# Hambmark_PCB-practice-STM32-two-wheel-ba.net
KiCad netlist of a schematic drawn in Altium Designer
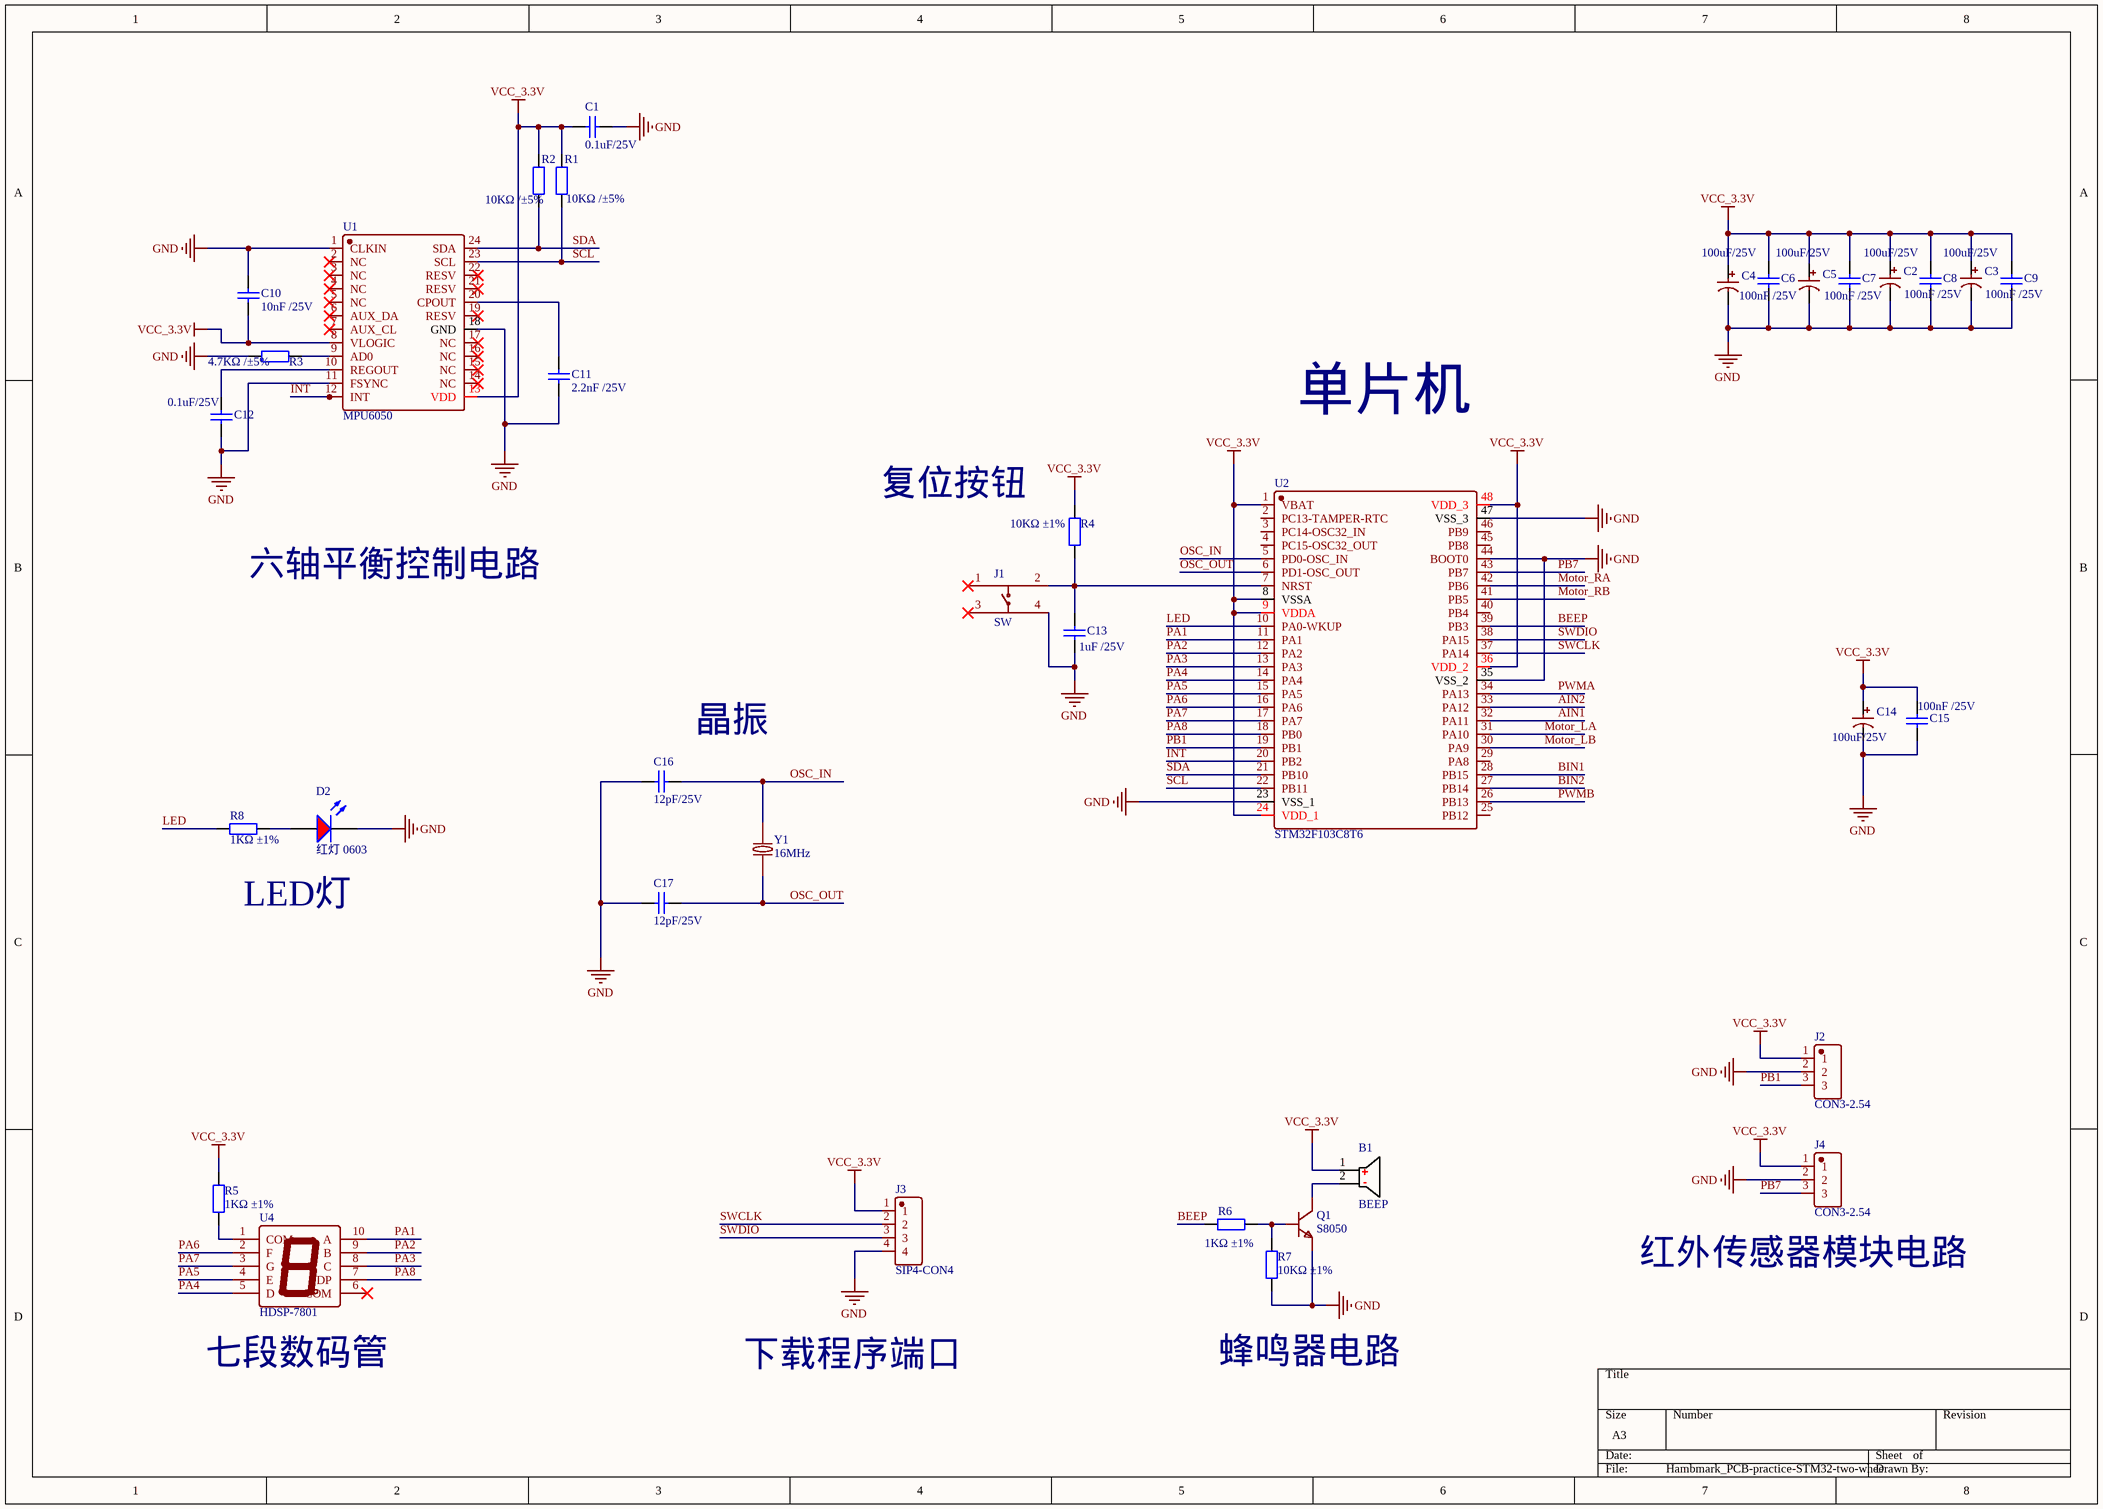
[diagram p0: Hambmark_PCB-practice-STM32-two-wheel-balancing-car__PRJ__2_BalanceControl.SchDoc]

(export (version "E")
  (design (tool "Eeschema 10.0.6"))
  (components
    (comp (ref "B1") (value "BEEP") (footprint "BEEP-9MM") (libsource (lib "Other") (part "BEEP")))
    (comp (ref "C1")
      (value "0.1uF/25V")
      (footprint "C0603")
      (description "贴片电容")
      (libsource (lib "Cap") (part "1206 100nF (104) 10% 50V"))
    )
    (comp (ref "C2") (value "100uF/25V") (footprint "C0603") (libsource (lib "Other") (part "100uF/25V")))
    (comp (ref "C3") (value "100uF/25V") (footprint "C0603") (libsource (lib "Other") (part "100uF/25V")))
    (comp (ref "C4") (value "100uF/25V") (footprint "C0603") (libsource (lib "Other") (part "100uF/25V")))
    (comp (ref "C5") (value "100uF/25V") (footprint "C0603") (libsource (lib "Other") (part "100uF/25V")))
    (comp (ref "C6")
      (value "100nF /25V")
      (footprint "C0603")
      (description "贴片电容")
      (libsource (lib "Cap") (part "0402 20pF (200) 5% 50V"))
    )
    (comp (ref "C7")
      (value "100nF /25V")
      (footprint "C0603")
      (description "贴片电容")
      (libsource (lib "Cap") (part "0402 20pF (200) 5% 50V"))
    )
    (comp (ref "C8")
      (value "100nF /25V")
      (footprint "C0603")
      (description "贴片电容")
      (libsource (lib "Cap") (part "0402 20pF (200) 5% 50V"))
    )
    (comp (ref "C9")
      (value "100nF /25V")
      (footprint "C0603")
      (description "贴片电容")
      (libsource (lib "Cap") (part "0402 20pF (200) 5% 50V"))
    )
    (comp (ref "C10")
      (value "10nF /25V")
      (footprint "C0603")
      (description "贴片电容")
      (libsource (lib "Cap") (part "1206 100nF (104) 10% 50V"))
    )
    (comp (ref "C11")
      (value "2.2nF /25V")
      (footprint "C0603")
      (description "贴片电容")
      (libsource (lib "Cap") (part "1206 100nF (104) 10% 50V"))
    )
    (comp (ref "C12")
      (value "0.1uF/25V")
      (footprint "C0603")
      (description "贴片电容")
      (libsource (lib "Cap") (part "1206 100nF (104) 10% 50V"))
    )
    (comp (ref "C13")
      (value "1uF /25V")
      (footprint "C0603")
      (description "贴片电容")
      (libsource (lib "Cap") (part "0402 20pF (200) 5% 50V"))
    )
    (comp (ref "C14") (value "100uF/25V") (footprint "C0603") (libsource (lib "Other") (part "100uF/25V")))
    (comp (ref "C15")
      (value "100nF /25V")
      (footprint "C0603")
      (description "贴片电容")
      (libsource (lib "Cap") (part "1206 100nF (104) 10% 50V"))
    )
    (comp (ref "C16")
      (value "12pF/25V")
      (footprint "C0603")
      (description "贴片电容")
      (libsource (lib "Cap") (part "0805 100nF(104) 10% 50V"))
    )
    (comp (ref "C17")
      (value "12pF/25V")
      (footprint "C0603")
      (description "贴片电容")
      (libsource (lib "Cap") (part "0805 100nF(104) 10% 50V"))
    )
    (comp (ref "D2")
      (value "红灯 0603")
      (footprint "LED-0603_S1")
      (description "发光二极管")
      (libsource (lib "LED") (part "0603 红灯"))
    )
    (comp (ref "J1") (value "SW") (footprint "SW-SMD_4P-L6.0-W6.0") (libsource (lib "Other") (part "SW")))
    (comp (ref "J2")
      (value "CON3-2.54")
      (footprint "DIP-3P-2.54-W")
      (libsource (lib "Other") (part "CON3-2.54"))
    )
    (comp (ref "J3")
      (value "SIP4-CON4")
      (footprint "DIP-4P-2.54-N")
      (libsource (lib "Other") (part "SIP4-CON4"))
    )
    (comp (ref "J4")
      (value "CON3-2.54")
      (footprint "DIP-3P-2.54-W")
      (libsource (lib "Other") (part "CON3-2.54"))
    )
    (comp (ref "Q1") (value "S8050") (footprint "SOT-23-3") (libsource (lib "Other") (part "S8050")))
    (comp (ref "R1")
      (value "10KΩ /±5%")
      (footprint "R0603")
      (description "贴片电阻")
      (libsource (lib "") (part "0402 0Ω (0R0) 1%_1"))
    )
    (comp (ref "R2")
      (value "10KΩ /±5%")
      (footprint "R0603")
      (description "贴片电阻")
      (libsource (lib "") (part "0402 0Ω (0R0) 1%_1"))
    )
    (comp (ref "R3")
      (value "4.7KΩ /±5%")
      (footprint "R0603")
      (description "贴片电阻")
      (libsource (lib "RES") (part "0402 0Ω (0R0) 1%"))
    )
    (comp (ref "R4")
      (value "10KΩ ±1%")
      (footprint "R0603")
      (description "贴片电阻")
      (libsource (lib "") (part "0402 0Ω (0R0) 1%_1"))
    )
    (comp (ref "R5")
      (value "1KΩ ±1%")
      (footprint "R0603")
      (description "贴片电阻")
      (libsource (lib "RES") (part "0603 1KΩ (1001) 1%"))
    )
    (comp (ref "R6")
      (value "1KΩ ±1%")
      (footprint "R0603")
      (description "贴片电阻")
      (libsource (lib "") (part "0603 1KΩ (1001) 1%_1"))
    )
    (comp (ref "R7")
      (value "10KΩ ±1%")
      (footprint "R0603")
      (description "贴片电阻")
      (libsource (lib "") (part "0603 1KΩ (1001) 1%_3"))
    )
    (comp (ref "R8")
      (value "1KΩ ±1%")
      (footprint "R0603")
      (description "贴片电阻")
      (libsource (lib "") (part "0603 1KΩ (1001) 1%_2"))
    )
    (comp (ref "U1")
      (value "MPU6050")
      (footprint "QFN-24_L4.0-W4.0-P0.50-BL")
      (libsource (lib "Other") (part "MPU6050"))
    )
    (comp (ref "U2")
      (value "STM32F103C8T6")
      (footprint "LQFP-48_L7.0-W7.0")
      (libsource (lib "Other") (part "STM32F103C8T6"))
    )
    (comp (ref "U4")
      (value "HDSP-7801")
      (footprint "LED-SEG-SMD_HDSP-7801")
      (libsource (lib "Other") (part "HDSP-7801"))
    )
    (comp (ref "Y1")
      (value "16MHz")
      (footprint "CRYSTAL-SMD_L3.2-W1.5")
      (libsource (lib "Other") (part "FC-135R 32.7680KF"))
    )
  )
  (nets
    (net (code "1") (name "/AIN1") (class "Default")
      (node (ref "U2") (pin "32") (pinfunction "PA11_32") (pintype "passive"))
    )
    (net (code "2") (name "/AIN2") (class "Default")
      (node (ref "U2") (pin "33") (pinfunction "PA12_33") (pintype "passive"))
    )
    (net (code "3") (name "/BEEP") (class "Default")
      (node (ref "R6") (pin "1") (pinfunction "1_1") (pintype "passive"))
      (node (ref "U2") (pin "39") (pinfunction "PB3_39") (pintype "passive"))
    )
    (net (code "4") (name "/BIN1") (class "Default")
      (node (ref "U2") (pin "28") (pinfunction "PB15_28") (pintype "passive"))
    )
    (net (code "5") (name "/BIN2") (class "Default")
      (node (ref "U2") (pin "27") (pinfunction "PB14_27") (pintype "passive"))
    )
    (net (code "6") (name "/INT") (class "Default")
      (node (ref "U1") (pin "12") (pinfunction "INT_12") (pintype "passive"))
      (node (ref "U2") (pin "20") (pinfunction "PB2_20") (pintype "passive"))
    )
    (net (code "7") (name "/LED") (class "Default")
      (node (ref "R8") (pin "2") (pinfunction "2_2") (pintype "passive"))
      (node (ref "U2") (pin "10") (pinfunction "PA0-WKUP_10") (pintype "passive"))
    )
    (net (code "8") (name "/Motor_LA") (class "Default")
      (node (ref "U2") (pin "31") (pinfunction "PA10_31") (pintype "passive"))
    )
    (net (code "9") (name "/Motor_LB") (class "Default")
      (node (ref "U2") (pin "30") (pinfunction "PA9_30") (pintype "passive"))
    )
    (net (code "10") (name "/Motor_RA") (class "Default")
      (node (ref "U2") (pin "42") (pinfunction "PB6_42") (pintype "passive"))
    )
    (net (code "11") (name "/Motor_RB") (class "Default")
      (node (ref "U2") (pin "41") (pinfunction "PB5_41") (pintype "passive"))
    )
    (net (code "12") (name "/OSC_IN") (class "Default")
      (node (ref "C16") (pin "1") (pinfunction "1_1") (pintype "passive"))
      (node (ref "U2") (pin "5") (pinfunction "PD0-OSC_IN_5") (pintype "passive"))
      (node (ref "Y1") (pin "2") (pinfunction "2_2") (pintype "passive"))
    )
    (net (code "13") (name "/OSC_OUT") (class "Default")
      (node (ref "C17") (pin "1") (pinfunction "1_1") (pintype "passive"))
      (node (ref "U2") (pin "6") (pinfunction "PD1-OSC_OUT_6") (pintype "passive"))
      (node (ref "Y1") (pin "1") (pinfunction "1_1") (pintype "passive"))
    )
    (net (code "14") (name "/PA1") (class "Default")
      (node (ref "U2") (pin "11") (pinfunction "PA1_11") (pintype "passive"))
      (node (ref "U4") (pin "10") (pinfunction "A_10") (pintype "passive"))
    )
    (net (code "15") (name "/PA2") (class "Default")
      (node (ref "U2") (pin "12") (pinfunction "PA2_12") (pintype "passive"))
      (node (ref "U4") (pin "9") (pinfunction "B_9") (pintype "passive"))
    )
    (net (code "16") (name "/PA3") (class "Default")
      (node (ref "U2") (pin "13") (pinfunction "PA3_13") (pintype "passive"))
      (node (ref "U4") (pin "8") (pinfunction "C_8") (pintype "passive"))
    )
    (net (code "17") (name "/PA4") (class "Default")
      (node (ref "U2") (pin "14") (pinfunction "PA4_14") (pintype "passive"))
      (node (ref "U4") (pin "5") (pinfunction "D_5") (pintype "passive"))
    )
    (net (code "18") (name "/PA5") (class "Default")
      (node (ref "U2") (pin "15") (pinfunction "PA5_15") (pintype "passive"))
      (node (ref "U4") (pin "4") (pinfunction "E_4") (pintype "passive"))
    )
    (net (code "19") (name "/PA6") (class "Default")
      (node (ref "U2") (pin "16") (pinfunction "PA6_16") (pintype "passive"))
      (node (ref "U4") (pin "2") (pinfunction "F_2") (pintype "passive"))
    )
    (net (code "20") (name "/PA7") (class "Default")
      (node (ref "U2") (pin "17") (pinfunction "PA7_17") (pintype "passive"))
      (node (ref "U4") (pin "3") (pinfunction "G_3") (pintype "passive"))
    )
    (net (code "21") (name "/PA8") (class "Default")
      (node (ref "U2") (pin "18") (pinfunction "PB0_18") (pintype "passive"))
      (node (ref "U4") (pin "7") (pinfunction "DP_7") (pintype "passive"))
    )
    (net (code "22") (name "/PB1") (class "Default")
      (node (ref "J2") (pin "3") (pinfunction "3_3") (pintype "passive"))
      (node (ref "U2") (pin "19") (pinfunction "PB1_19") (pintype "passive"))
    )
    (net (code "23") (name "/PB7") (class "Default")
      (node (ref "J4") (pin "3") (pinfunction "3_3") (pintype "passive"))
      (node (ref "U2") (pin "43") (pinfunction "PB7_43") (pintype "passive"))
    )
    (net (code "24") (name "/PWMA") (class "Default")
      (node (ref "U2") (pin "34") (pinfunction "PA13_34") (pintype "passive"))
    )
    (net (code "25") (name "/PWMB") (class "Default")
      (node (ref "U2") (pin "26") (pinfunction "PB13_26") (pintype "passive"))
    )
    (net (code "26") (name "/SCL") (class "Default")
      (node (ref "R1") (pin "1") (pinfunction "1_1") (pintype "passive"))
      (node (ref "U1") (pin "23") (pinfunction "SCL_23") (pintype "passive"))
      (node (ref "U2") (pin "22") (pinfunction "PB11_22") (pintype "passive"))
    )
    (net (code "27") (name "/SDA") (class "Default")
      (node (ref "R2") (pin "1") (pinfunction "1_1") (pintype "passive"))
      (node (ref "U1") (pin "24") (pinfunction "SDA_24") (pintype "passive"))
      (node (ref "U2") (pin "21") (pinfunction "PB10_21") (pintype "passive"))
    )
    (net (code "28") (name "/SWCLK") (class "Default")
      (node (ref "J3") (pin "2") (pinfunction "2_2") (pintype "passive"))
      (node (ref "U2") (pin "37") (pinfunction "PA14_37") (pintype "passive"))
    )
    (net (code "29") (name "/SWDIO") (class "Default")
      (node (ref "J3") (pin "3") (pinfunction "3_3") (pintype "passive"))
      (node (ref "U2") (pin "38") (pinfunction "PA15_38") (pintype "passive"))
    )
    (net (code "30") (name "GND") (class "Default")
      (node (ref "C1") (pin "2") (pinfunction "2_2") (pintype "passive"))
      (node (ref "C10") (pin "2") (pinfunction "2_2") (pintype "passive"))
      (node (ref "C11") (pin "1") (pinfunction "1_1") (pintype "passive"))
      (node (ref "C12") (pin "1") (pinfunction "1_1") (pintype "passive"))
      (node (ref "C13") (pin "2") (pinfunction "2_2") (pintype "passive"))
      (node (ref "C14") (pin "2") (pinfunction "2_2") (pintype "passive"))
      (node (ref "C15") (pin "1") (pinfunction "1_1") (pintype "passive"))
      (node (ref "C16") (pin "2") (pinfunction "2_2") (pintype "passive"))
      (node (ref "C17") (pin "2") (pinfunction "2_2") (pintype "passive"))
      (node (ref "C2") (pin "2") (pinfunction "2_2") (pintype "passive"))
      (node (ref "C3") (pin "2") (pinfunction "2_2") (pintype "passive"))
      (node (ref "C4") (pin "2") (pinfunction "2_2") (pintype "passive"))
      (node (ref "C5") (pin "2") (pinfunction "2_2") (pintype "passive"))
      (node (ref "C6") (pin "1") (pinfunction "1_1") (pintype "passive"))
      (node (ref "C7") (pin "1") (pinfunction "1_1") (pintype "passive"))
      (node (ref "C8") (pin "1") (pinfunction "1_1") (pintype "passive"))
      (node (ref "C9") (pin "1") (pinfunction "1_1") (pintype "passive"))
      (node (ref "D2") (pin "K") (pinfunction "K_K") (pintype "passive"))
      (node (ref "J1") (pin "4") (pinfunction "4_4") (pintype "passive"))
      (node (ref "J2") (pin "2") (pinfunction "2_2") (pintype "passive"))
      (node (ref "J3") (pin "4") (pinfunction "4_4") (pintype "passive"))
      (node (ref "J4") (pin "2") (pinfunction "2_2") (pintype "passive"))
      (node (ref "Q1") (pin "2") (pinfunction "E_2") (pintype "passive"))
      (node (ref "R3") (pin "2") (pinfunction "2_2") (pintype "passive"))
      (node (ref "R7") (pin "1") (pinfunction "1_1") (pintype "passive"))
      (node (ref "U1") (pin "1") (pinfunction "CLKIN_1") (pintype "passive"))
      (node (ref "U1") (pin "11") (pinfunction "FSYNC_11") (pintype "passive"))
      (node (ref "U1") (pin "18") (pinfunction "GND_18") (pintype "passive"))
      (node (ref "U2") (pin "23") (pinfunction "VSS_1_23") (pintype "passive"))
      (node (ref "U2") (pin "35") (pinfunction "VSS_2_35") (pintype "passive"))
      (node (ref "U2") (pin "44") (pinfunction "BOOT0_44") (pintype "passive"))
      (node (ref "U2") (pin "47") (pinfunction "VSS_3_47") (pintype "passive"))
    )
    (net (code "31") (name "Net-(D2-PadA)") (class "Default")
      (node (ref "D2") (pin "A") (pinfunction "A_A") (pintype "passive"))
      (node (ref "R8") (pin "1") (pinfunction "1_1") (pintype "passive"))
    )
    (net (code "32") (name "Net-(Q1-B)") (class "Default")
      (node (ref "Q1") (pin "1") (pinfunction "B_1") (pintype "passive"))
      (node (ref "R6") (pin "2") (pinfunction "2_2") (pintype "passive"))
      (node (ref "R7") (pin "2") (pinfunction "2_2") (pintype "passive"))
    )
    (net (code "33") (name "Net-(Q1-C)") (class "Default")
      (node (ref "B1") (pin "2") (pinfunction "2_2") (pintype "passive"))
      (node (ref "Q1") (pin "3") (pinfunction "C_3") (pintype "passive"))
    )
    (net (code "34") (name "Net-(R5-Pad2)") (class "Default")
      (node (ref "R5") (pin "2") (pinfunction "2_2") (pintype "passive"))
      (node (ref "U4") (pin "1") (pinfunction "COM_1") (pintype "passive"))
    )
    (net (code "35") (name "Net-(U1-AD0)") (class "Default")
      (node (ref "R3") (pin "1") (pinfunction "1_1") (pintype "passive"))
      (node (ref "U1") (pin "9") (pinfunction "AD0_9") (pintype "passive"))
    )
    (net (code "36") (name "Net-(U1-CPOUT)") (class "Default")
      (node (ref "C11") (pin "2") (pinfunction "2_2") (pintype "passive"))
      (node (ref "U1") (pin "20") (pinfunction "CPOUT_20") (pintype "passive"))
    )
    (net (code "37") (name "Net-(U1-REGOUT)") (class "Default")
      (node (ref "C12") (pin "2") (pinfunction "2_2") (pintype "passive"))
      (node (ref "U1") (pin "10") (pinfunction "REGOUT_10") (pintype "passive"))
    )
    (net (code "38") (name "Net-(U2-NRST)") (class "Default")
      (node (ref "C13") (pin "1") (pinfunction "1_1") (pintype "passive"))
      (node (ref "J1") (pin "2") (pinfunction "2_2") (pintype "passive"))
      (node (ref "R4") (pin "1") (pinfunction "1_1") (pintype "passive"))
      (node (ref "U2") (pin "7") (pinfunction "NRST_7") (pintype "passive"))
    )
    (net (code "39") (name "VCC_3.3V") (class "Default")
      (node (ref "B1") (pin "1") (pinfunction "1_1") (pintype "passive"))
      (node (ref "C1") (pin "1") (pinfunction "1_1") (pintype "passive"))
      (node (ref "C10") (pin "1") (pinfunction "1_1") (pintype "passive"))
      (node (ref "C14") (pin "1") (pinfunction "1_1") (pintype "passive"))
      (node (ref "C15") (pin "2") (pinfunction "2_2") (pintype "passive"))
      (node (ref "C2") (pin "1") (pinfunction "1_1") (pintype "passive"))
      (node (ref "C3") (pin "1") (pinfunction "1_1") (pintype "passive"))
      (node (ref "C4") (pin "1") (pinfunction "1_1") (pintype "passive"))
      (node (ref "C5") (pin "1") (pinfunction "1_1") (pintype "passive"))
      (node (ref "C6") (pin "2") (pinfunction "2_2") (pintype "passive"))
      (node (ref "C7") (pin "2") (pinfunction "2_2") (pintype "passive"))
      (node (ref "C8") (pin "2") (pinfunction "2_2") (pintype "passive"))
      (node (ref "C9") (pin "2") (pinfunction "2_2") (pintype "passive"))
      (node (ref "J2") (pin "1") (pinfunction "1_1") (pintype "passive"))
      (node (ref "J3") (pin "1") (pinfunction "1_1") (pintype "passive"))
      (node (ref "J4") (pin "1") (pinfunction "1_1") (pintype "passive"))
      (node (ref "R1") (pin "2") (pinfunction "2_2") (pintype "passive"))
      (node (ref "R2") (pin "2") (pinfunction "2_2") (pintype "passive"))
      (node (ref "R4") (pin "2") (pinfunction "2_2") (pintype "passive"))
      (node (ref "R5") (pin "1") (pinfunction "1_1") (pintype "passive"))
      (node (ref "U1") (pin "13") (pinfunction "VDD_13") (pintype "passive"))
      (node (ref "U1") (pin "8") (pinfunction "VLOGIC_8") (pintype "passive"))
      (node (ref "U2") (pin "1") (pinfunction "VBAT_1") (pintype "passive"))
      (node (ref "U2") (pin "24") (pinfunction "VDD_1_24") (pintype "passive"))
      (node (ref "U2") (pin "36") (pinfunction "VDD_2_36") (pintype "passive"))
      (node (ref "U2") (pin "48") (pinfunction "VDD_3_48") (pintype "passive"))
      (node (ref "U2") (pin "8") (pinfunction "VSSA_8") (pintype "passive"))
      (node (ref "U2") (pin "9") (pinfunction "VDDA_9") (pintype "passive"))
    )
    (net (code "40") (name "unconnected-(J1-Pad1)") (class "Default")
      (node (ref "J1") (pin "1") (pinfunction "1_1") (pintype "passive+no_connect"))
    )
    (net (code "41") (name "unconnected-(J1-Pad3)") (class "Default")
      (node (ref "J1") (pin "3") (pinfunction "3_3") (pintype "passive+no_connect"))
    )
    (net (code "42") (name "unconnected-(U1-AUX_CL-Pad7)") (class "Default")
      (node (ref "U1") (pin "7") (pinfunction "AUX_CL_7") (pintype "passive+no_connect"))
    )
    (net (code "43") (name "unconnected-(U1-AUX_DA-Pad6)") (class "Default")
      (node (ref "U1") (pin "6") (pinfunction "AUX_DA_6") (pintype "passive+no_connect"))
    )
    (net (code "44") (name "unconnected-(U1-NC-Pad2)") (class "Default")
      (node (ref "U1") (pin "2") (pinfunction "NC_2") (pintype "passive+no_connect"))
    )
    (net (code "45") (name "unconnected-(U1-NC-Pad3)") (class "Default")
      (node (ref "U1") (pin "3") (pinfunction "NC_3") (pintype "passive+no_connect"))
    )
    (net (code "46") (name "unconnected-(U1-NC-Pad4)") (class "Default")
      (node (ref "U1") (pin "4") (pinfunction "NC_4") (pintype "passive+no_connect"))
    )
    (net (code "47") (name "unconnected-(U1-NC-Pad5)") (class "Default")
      (node (ref "U1") (pin "5") (pinfunction "NC_5") (pintype "passive+no_connect"))
    )
    (net (code "48") (name "unconnected-(U1-NC-Pad14)") (class "Default")
      (node (ref "U1") (pin "14") (pinfunction "NC_14") (pintype "passive+no_connect"))
    )
    (net (code "49") (name "unconnected-(U1-NC-Pad15)") (class "Default")
      (node (ref "U1") (pin "15") (pinfunction "NC_15") (pintype "passive+no_connect"))
    )
    (net (code "50") (name "unconnected-(U1-NC-Pad16)") (class "Default")
      (node (ref "U1") (pin "16") (pinfunction "NC_16") (pintype "passive+no_connect"))
    )
    (net (code "51") (name "unconnected-(U1-NC-Pad17)") (class "Default")
      (node (ref "U1") (pin "17") (pinfunction "NC_17") (pintype "passive+no_connect"))
    )
    (net (code "52") (name "unconnected-(U1-RESV-Pad19)") (class "Default")
      (node (ref "U1") (pin "19") (pinfunction "RESV_19") (pintype "passive+no_connect"))
    )
    (net (code "53") (name "unconnected-(U1-RESV-Pad21)") (class "Default")
      (node (ref "U1") (pin "21") (pinfunction "RESV_21") (pintype "passive+no_connect"))
    )
    (net (code "54") (name "unconnected-(U1-RESV-Pad22)") (class "Default")
      (node (ref "U1") (pin "22") (pinfunction "RESV_22") (pintype "passive+no_connect"))
    )
    (net (code "55") (name "unconnected-(U2-PA8-Pad29)") (class "Default")
      (node (ref "U2") (pin "29") (pinfunction "PA8_29") (pintype "passive"))
    )
    (net (code "56") (name "unconnected-(U2-PB4-Pad40)") (class "Default")
      (node (ref "U2") (pin "40") (pinfunction "PB4_40") (pintype "passive"))
    )
    (net (code "57") (name "unconnected-(U2-PB8-Pad45)") (class "Default")
      (node (ref "U2") (pin "45") (pinfunction "PB8_45") (pintype "passive"))
    )
    (net (code "58") (name "unconnected-(U2-PB9-Pad46)") (class "Default")
      (node (ref "U2") (pin "46") (pinfunction "PB9_46") (pintype "passive"))
    )
    (net (code "59") (name "unconnected-(U2-PB12-Pad25)") (class "Default")
      (node (ref "U2") (pin "25") (pinfunction "PB12_25") (pintype "passive"))
    )
    (net (code "60") (name "unconnected-(U2-PC13-TAMPER-RTC-Pad2)") (class "Default")
      (node (ref "U2") (pin "2") (pinfunction "PC13-TAMPER-RTC_2") (pintype "passive"))
    )
    (net (code "61") (name "unconnected-(U2-PC14-OSC32_IN-Pad3)") (class "Default")
      (node (ref "U2") (pin "3") (pinfunction "PC14-OSC32_IN_3") (pintype "passive"))
    )
    (net (code "62") (name "unconnected-(U2-PC15-OSC32_OUT-Pad4)") (class "Default")
      (node (ref "U2") (pin "4") (pinfunction "PC15-OSC32_OUT_4") (pintype "passive"))
    )
    (net (code "63") (name "unconnected-(U4-COM-Pad6)") (class "Default")
      (node (ref "U4") (pin "6") (pinfunction "COM_6") (pintype "passive+no_connect"))
    )
  )
)
